# LispStar.net
KiCad netlist of a schematic drawn in EAGLE
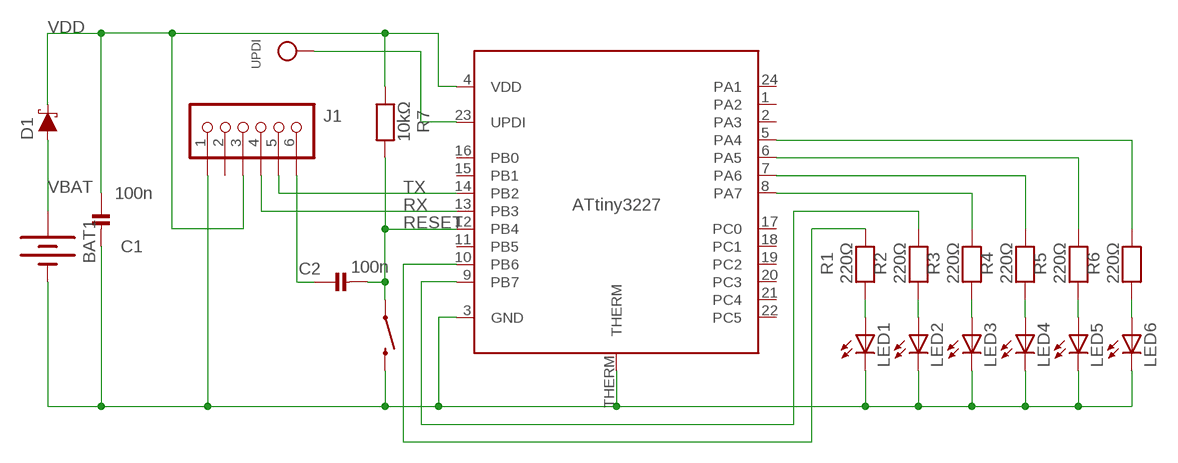
[diagram p0: schematic, sheet 1]

(export (version "E")
  (design (tool "Eeschema 10.0.6"))
  (components
    (comp (ref "BAT1")
      (value "BATTERY12MM")
      (footprint "eagle-import:BATTCON_12MM")
      (libsource (lib "eagle-import") (part "BATTERY12MM"))
    )
    (comp (ref "C1")
      (value "100n")
      (footprint "eagle-import:_0805MP")
      (libsource (lib "eagle-import") (part "CAP_CERAMIC_0805MP"))
    )
    (comp (ref "C2")
      (value "100n")
      (footprint "eagle-import:_0805MP")
      (libsource (lib "eagle-import") (part "CAP_CERAMIC_0805MP"))
    )
    (comp (ref "D1")
      (value "3A/10V/280mV")
      (footprint "eagle-import:SOD-323")
      (libsource (lib "eagle-import") (part "DIODE-SCHOTTKY-BAT60A"))
    )
    (comp (ref "J1")
      (value "AVR_SPI_PRG_6LINETESTPOINTS")
      (footprint "eagle-import:2X3_TEST_POINTS")
      (libsource (lib "eagle-import") (part "AVR_SPI_PRG_6LINETESTPOINTS"))
    )
    (comp (ref "LED1")
      (value "LEDCHIPLED_0805")
      (footprint "eagle-import:CHIPLED_0805")
      (libsource (lib "eagle-import") (part "LEDCHIPLED_0805"))
    )
    (comp (ref "LED2")
      (value "LEDCHIPLED_0805")
      (footprint "eagle-import:CHIPLED_0805")
      (libsource (lib "eagle-import") (part "LEDCHIPLED_0805"))
    )
    (comp (ref "LED3")
      (value "LEDCHIPLED_0805")
      (footprint "eagle-import:CHIPLED_0805")
      (libsource (lib "eagle-import") (part "LEDCHIPLED_0805"))
    )
    (comp (ref "LED4")
      (value "LEDCHIPLED_0805")
      (footprint "eagle-import:CHIPLED_0805")
      (libsource (lib "eagle-import") (part "LEDCHIPLED_0805"))
    )
    (comp (ref "LED5")
      (value "LEDCHIPLED_0805")
      (footprint "eagle-import:CHIPLED_0805")
      (libsource (lib "eagle-import") (part "LEDCHIPLED_0805"))
    )
    (comp (ref "LED6")
      (value "LEDCHIPLED_0805")
      (footprint "eagle-import:CHIPLED_0805")
      (libsource (lib "eagle-import") (part "LEDCHIPLED_0805"))
    )
    (comp (ref "R1")
      (value "220Ω")
      (footprint "eagle-import:_0805MP")
      (libsource (lib "eagle-import") (part "RESISTOR_0805MP"))
    )
    (comp (ref "R2")
      (value "220Ω")
      (footprint "eagle-import:_0805MP")
      (libsource (lib "eagle-import") (part "RESISTOR_0805MP"))
    )
    (comp (ref "R3")
      (value "220Ω")
      (footprint "eagle-import:_0805MP")
      (libsource (lib "eagle-import") (part "RESISTOR_0805MP"))
    )
    (comp (ref "R4")
      (value "220Ω")
      (footprint "eagle-import:_0805MP")
      (libsource (lib "eagle-import") (part "RESISTOR_0805MP"))
    )
    (comp (ref "R5")
      (value "220Ω")
      (footprint "eagle-import:_0805MP")
      (libsource (lib "eagle-import") (part "RESISTOR_0805MP"))
    )
    (comp (ref "R6")
      (value "220Ω")
      (footprint "eagle-import:_0805MP")
      (libsource (lib "eagle-import") (part "RESISTOR_0805MP"))
    )
    (comp (ref "R7")
      (value "10kΩ")
      (footprint "eagle-import:_0805MP")
      (libsource (lib "eagle-import") (part "RESISTOR_0805MP"))
    )
    (comp (ref "S2")
      (value "SWITCH-MOMENTARY-2SMD")
      (footprint "eagle-import:TACTILE-SWITCH-SMD")
      (libsource (lib "eagle-import") (part "SWITCH-MOMENTARY-2SMD"))
    )
    (comp (ref "U1")
      (value "ATtiny3227")
      (footprint "eagle-import:QFN24_4MM")
      (libsource (lib "eagle-import") (part "ATTINY3227"))
    )
    (comp (ref "UPDI")
      (value "TESTPOINTROUND1MM")
      (footprint "eagle-import:TESTPOINT_ROUND_1MM")
      (libsource (lib "eagle-import") (part "TESTPOINTROUND1MM"))
    )
  )
  (nets
    (net (code "1") (name "Net-(BAT1--)") (class "Default")
      (node (ref "BAT1") (pin "GND") (pinfunction "-_GND") (pintype "power_in"))
      (node (ref "C1") (pin "2") (pinfunction "P$2_2") (pintype "passive"))
      (node (ref "J1") (pin "1") (pinfunction "1_1") (pintype "passive"))
      (node (ref "LED1") (pin "C") (pinfunction "C_C") (pintype "passive"))
      (node (ref "LED2") (pin "C") (pinfunction "C_C") (pintype "passive"))
      (node (ref "LED3") (pin "C") (pinfunction "C_C") (pintype "passive"))
      (node (ref "LED4") (pin "C") (pinfunction "C_C") (pintype "passive"))
      (node (ref "LED5") (pin "C") (pinfunction "C_C") (pintype "passive"))
      (node (ref "LED6") (pin "C") (pinfunction "C_C") (pintype "passive"))
      (node (ref "S2") (pin "3") (pinfunction "2_3") (pintype "passive"))
      (node (ref "U1") (pin "3") (pinfunction "GND_3") (pintype "power_in"))
      (node (ref "U1") (pin "THERM") (pinfunction "THERM_THERM") (pintype "power_in"))
    )
    (net (code "2") (name "Net-(C2-P$1)") (class "Default")
      (node (ref "C2") (pin "1") (pinfunction "P$1_1") (pintype "passive"))
      (node (ref "J1") (pin "6") (pinfunction "6_6") (pintype "passive"))
    )
    (net (code "3") (name "Net-(LED1-PadA)") (class "Default")
      (node (ref "LED1") (pin "A") (pinfunction "A_A") (pintype "passive"))
      (node (ref "R1") (pin "1") (pinfunction "1_1") (pintype "passive"))
    )
    (net (code "4") (name "Net-(LED2-PadA)") (class "Default")
      (node (ref "LED2") (pin "A") (pinfunction "A_A") (pintype "passive"))
      (node (ref "R2") (pin "1") (pinfunction "1_1") (pintype "passive"))
    )
    (net (code "5") (name "Net-(LED3-PadA)") (class "Default")
      (node (ref "LED3") (pin "A") (pinfunction "A_A") (pintype "passive"))
      (node (ref "R3") (pin "1") (pinfunction "1_1") (pintype "passive"))
    )
    (net (code "6") (name "Net-(LED4-PadA)") (class "Default")
      (node (ref "LED4") (pin "A") (pinfunction "A_A") (pintype "passive"))
      (node (ref "R4") (pin "1") (pinfunction "1_1") (pintype "passive"))
    )
    (net (code "7") (name "Net-(LED5-PadA)") (class "Default")
      (node (ref "LED5") (pin "A") (pinfunction "A_A") (pintype "passive"))
      (node (ref "R5") (pin "1") (pinfunction "1_1") (pintype "passive"))
    )
    (net (code "8") (name "Net-(LED6-PadA)") (class "Default")
      (node (ref "LED6") (pin "A") (pinfunction "A_A") (pintype "passive"))
      (node (ref "R6") (pin "1") (pinfunction "1_1") (pintype "passive"))
    )
    (net (code "9") (name "Net-(U1-PA4)") (class "Default")
      (node (ref "R6") (pin "2") (pinfunction "2_2") (pintype "passive"))
      (node (ref "U1") (pin "5") (pinfunction "PA4_5") (pintype "bidirectional"))
    )
    (net (code "10") (name "Net-(U1-PA5)") (class "Default")
      (node (ref "R5") (pin "2") (pinfunction "2_2") (pintype "passive"))
      (node (ref "U1") (pin "6") (pinfunction "PA5_6") (pintype "bidirectional"))
    )
    (net (code "11") (name "Net-(U1-PA6)") (class "Default")
      (node (ref "R4") (pin "2") (pinfunction "2_2") (pintype "passive"))
      (node (ref "U1") (pin "7") (pinfunction "PA6_7") (pintype "bidirectional"))
    )
    (net (code "12") (name "Net-(U1-PA7)") (class "Default")
      (node (ref "R3") (pin "2") (pinfunction "2_2") (pintype "passive"))
      (node (ref "U1") (pin "8") (pinfunction "PA7_8") (pintype "bidirectional"))
    )
    (net (code "13") (name "Net-(U1-PB6)") (class "Default")
      (node (ref "R1") (pin "2") (pinfunction "2_2") (pintype "passive"))
      (node (ref "U1") (pin "10") (pinfunction "PB6_10") (pintype "bidirectional"))
    )
    (net (code "14") (name "Net-(U1-PB7)") (class "Default")
      (node (ref "R2") (pin "2") (pinfunction "2_2") (pintype "passive"))
      (node (ref "U1") (pin "9") (pinfunction "PB7_9") (pintype "bidirectional"))
    )
    (net (code "15") (name "Net-(U1-UPDI)") (class "Default")
      (node (ref "U1") (pin "23") (pinfunction "UPDI_23") (pintype "bidirectional"))
      (node (ref "UPDI") (pin "P$1") (pinfunction "P$1_P$1") (pintype "bidirectional"))
    )
    (net (code "16") (name "RESET") (class "Default")
      (node (ref "C2") (pin "2") (pinfunction "P$2_2") (pintype "passive"))
      (node (ref "R7") (pin "1") (pinfunction "1_1") (pintype "passive"))
      (node (ref "S2") (pin "1") (pinfunction "1_1") (pintype "passive"))
      (node (ref "U1") (pin "12") (pinfunction "PB4_12") (pintype "bidirectional"))
    )
    (net (code "17") (name "RX") (class "Default")
      (node (ref "J1") (pin "4") (pinfunction "4_4") (pintype "passive"))
      (node (ref "U1") (pin "13") (pinfunction "PB3_13") (pintype "bidirectional"))
    )
    (net (code "18") (name "TX") (class "Default")
      (node (ref "J1") (pin "5") (pinfunction "5_5") (pintype "passive"))
      (node (ref "U1") (pin "14") (pinfunction "PB2_14") (pintype "bidirectional"))
    )
    (net (code "19") (name "VBAT") (class "Default")
      (node (ref "BAT1") (pin "PWR@1") (pinfunction "+_PWR@1") (pintype "power_in"))
      (node (ref "D1") (pin "A") (pinfunction "A_A") (pintype "passive"))
    )
    (net (code "20") (name "VDD") (class "Default")
      (node (ref "C1") (pin "1") (pinfunction "P$1_1") (pintype "passive"))
      (node (ref "D1") (pin "C") (pinfunction "C_C") (pintype "passive"))
      (node (ref "J1") (pin "3") (pinfunction "3_3") (pintype "passive"))
      (node (ref "R7") (pin "2") (pinfunction "2_2") (pintype "passive"))
      (node (ref "U1") (pin "4") (pinfunction "VDD_4") (pintype "power_in"))
    )
    (net (code "21") (name "unconnected-(J1-Pad2)") (class "Default")
      (node (ref "J1") (pin "2") (pinfunction "2_2") (pintype "passive"))
    )
    (net (code "22") (name "unconnected-(U1-PA1-Pad24)") (class "Default")
      (node (ref "U1") (pin "24") (pinfunction "PA1_24") (pintype "bidirectional"))
    )
    (net (code "23") (name "unconnected-(U1-PA2-Pad1)") (class "Default")
      (node (ref "U1") (pin "1") (pinfunction "PA2_1") (pintype "bidirectional"))
    )
    (net (code "24") (name "unconnected-(U1-PA3-Pad2)") (class "Default")
      (node (ref "U1") (pin "2") (pinfunction "PA3_2") (pintype "bidirectional"))
    )
    (net (code "25") (name "unconnected-(U1-PB0-Pad16)") (class "Default")
      (node (ref "U1") (pin "16") (pinfunction "PB0_16") (pintype "bidirectional"))
    )
    (net (code "26") (name "unconnected-(U1-PB1-Pad15)") (class "Default")
      (node (ref "U1") (pin "15") (pinfunction "PB1_15") (pintype "bidirectional"))
    )
    (net (code "27") (name "unconnected-(U1-PB5-Pad11)") (class "Default")
      (node (ref "U1") (pin "11") (pinfunction "PB5_11") (pintype "bidirectional"))
    )
    (net (code "28") (name "unconnected-(U1-PC0-Pad17)") (class "Default")
      (node (ref "U1") (pin "17") (pinfunction "PC0_17") (pintype "bidirectional"))
    )
    (net (code "29") (name "unconnected-(U1-PC1-Pad18)") (class "Default")
      (node (ref "U1") (pin "18") (pinfunction "PC1_18") (pintype "bidirectional"))
    )
    (net (code "30") (name "unconnected-(U1-PC2-Pad19)") (class "Default")
      (node (ref "U1") (pin "19") (pinfunction "PC2_19") (pintype "bidirectional"))
    )
    (net (code "31") (name "unconnected-(U1-PC3-Pad20)") (class "Default")
      (node (ref "U1") (pin "20") (pinfunction "PC3_20") (pintype "bidirectional"))
    )
    (net (code "32") (name "unconnected-(U1-PC4-Pad21)") (class "Default")
      (node (ref "U1") (pin "21") (pinfunction "PC4_21") (pintype "bidirectional"))
    )
    (net (code "33") (name "unconnected-(U1-PC5-Pad22)") (class "Default")
      (node (ref "U1") (pin "22") (pinfunction "PC5_22") (pintype "bidirectional"))
    )
  )
)
